# 3V3_EPS.net
KiCad netlist of a schematic drawn in Altium Designer
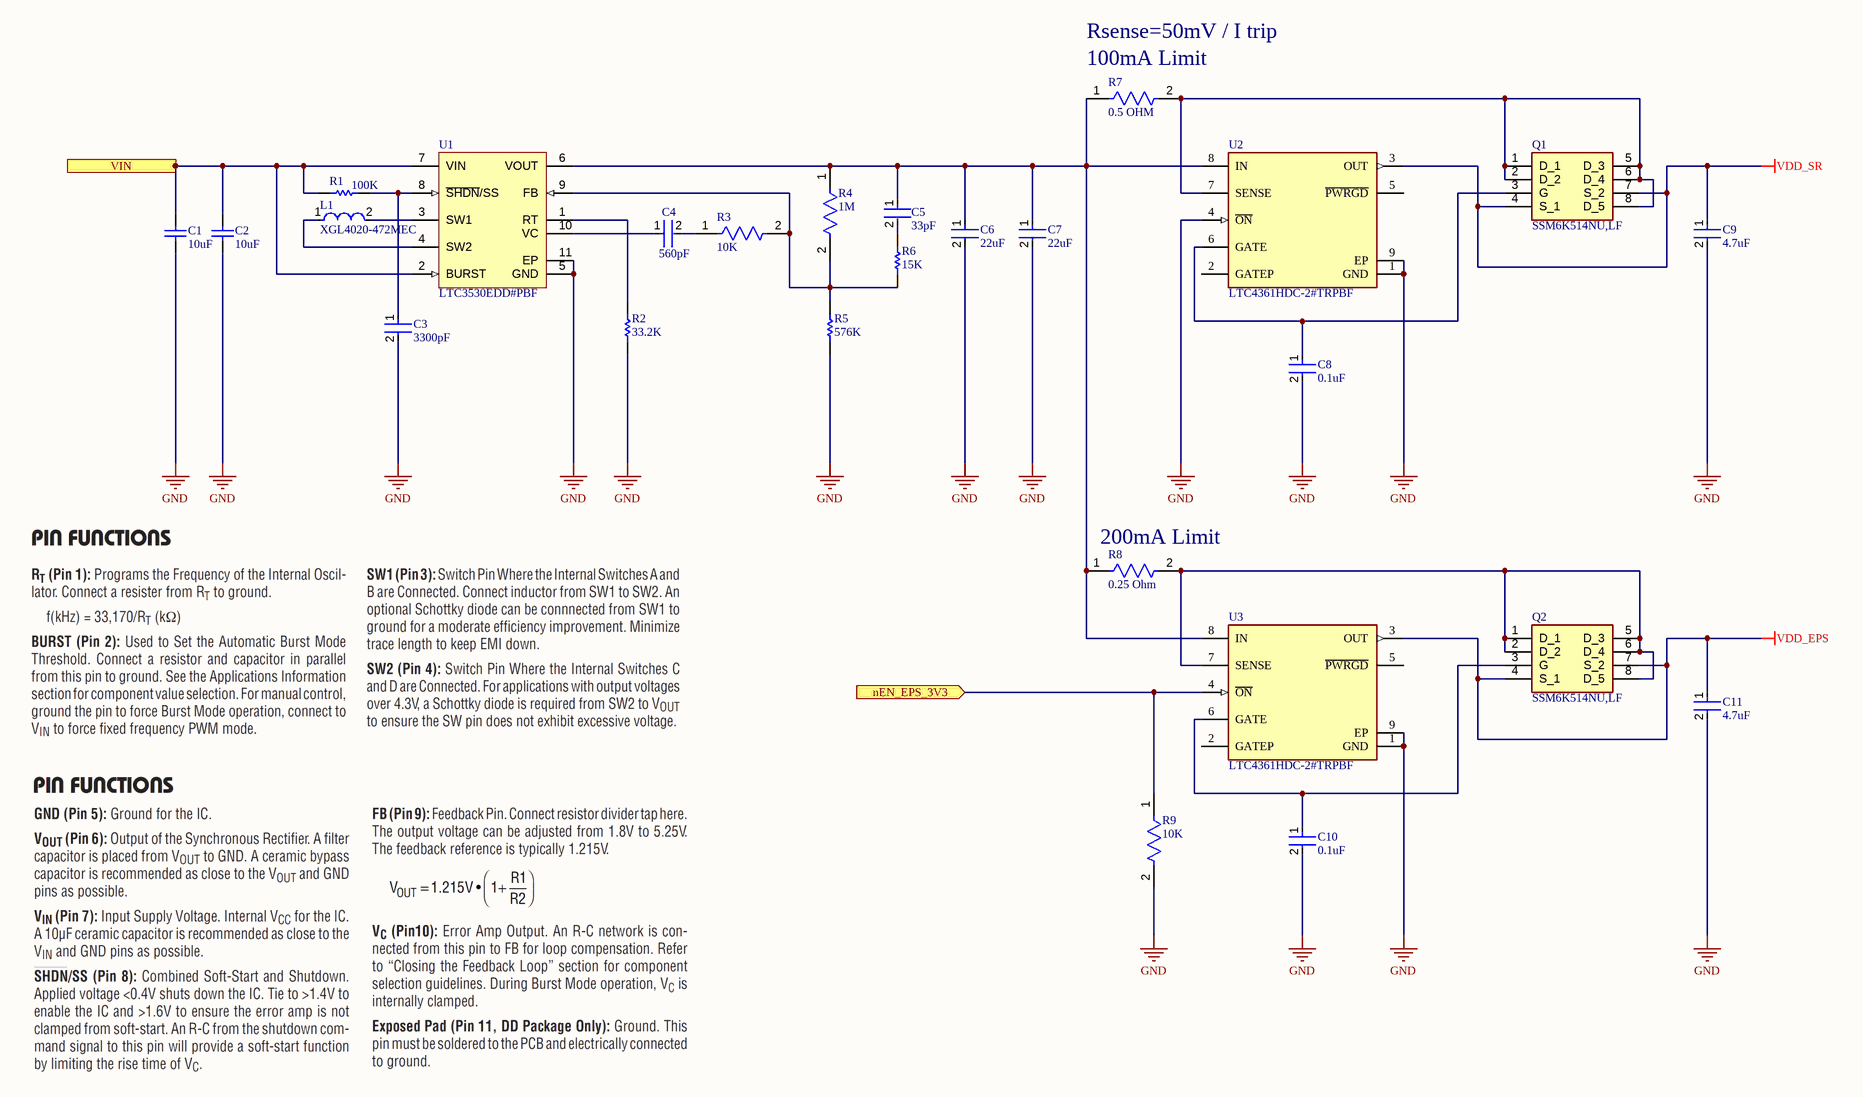
[diagram p0: 3V3_EPS.SchDoc]

(export (version "E")
  (design (tool "Eeschema 10.0.6"))
  (components
    (comp (ref "C1")
      (value "10uF")
      (footprint "CAPC2013X140X45NL15T25")
      (description "10uF 0805")
      (fields (field (name "PART NUMBER") "GRM21BR71A106KE51L") (field (name "MANUFACTURER") "Murata"))
      (libsource (lib "Altium Content Vault") (part "CAP"))
    )
    (comp (ref "C2")
      (value "10uF")
      (footprint "CAPC2013X140X45NL15T25")
      (description "10uF 0805")
      (fields (field (name "PART NUMBER") "GRM21BR71A106KE51L") (field (name "MANUFACTURER") "Murata"))
      (libsource (lib "Altium Content Vault") (part "CAP"))
    )
    (comp (ref "C3")
      (value "3300pF")
      (footprint "FP-C0603C-CF-MFG")
      (description "CAP CER 3300PF 50V 5% X7R 0603")
      (fields
        (field (name "MANUFACTURER PART NUMBER") "C0603C332J5RACTU")
        (field (name "MANUFACTURER") "KEMET")
      )
      (libsource (lib "Altium Content Vault") (part "b4654b650e69147ec39a6b967a45e02"))
    )
    (comp (ref "C4")
      (value "560pF")
      (footprint "FP-C0603C-CF-MFG")
      (description "CAP CER 560PF 50V X7R 0603")
      (fields
        (field (name "TOLERANCE") "0.1")
        (field (name "OCTOPART") "https://octopart.com/c0603c561k5ractu-kemet-138569")
      )
      (libsource (lib "Altium Content Vault") (part "b4654b650e69147ec39a6b967a45e02"))
    )
    (comp (ref "C5")
      (value "33pF")
      (footprint "FP-C0603C-CF-MFG")
      (description "CAP CER 33PF 16V X7R 0603")
      (fields
        (field (name "OCTOPART") "https://octopart.com/c0603c330k4rac7867-kemet-83501964")
        (field (name "MANUFACTURER PART NUMBER") "C0603C330K4RAC7867")
      )
      (libsource (lib "Altium Content Vault") (part "b4654b650e69147ec39a6b967a45e02"))
    )
    (comp (ref "C6")
      (value "22uF")
      (footprint "FP-GRM21B-0_2-e0_2_0_7-IPC_C")
      (description "Chip Multilayer Ceramic Capacitors for General Purpose, 0805, 22uF, X7T, +22%/-33%, 20%, 10V")
      (fields (field (name "VOLTAGE") "10V") (field (name "TOLERANCE") "20%"))
      (libsource (lib "Altium Content Vault") (part "b4654b650e69147ec39a6b967a45e02"))
    )
    (comp (ref "C7")
      (value "22uF")
      (footprint "FP-GRM21B-0_2-e0_2_0_7-IPC_C")
      (description "Chip Multilayer Ceramic Capacitors for General Purpose, 0805, 22uF, X7T, +22%/-33%, 20%, 10V")
      (fields (field (name "VOLTAGE") "10V") (field (name "TOLERANCE") "20%"))
      (libsource (lib "Altium Content Vault") (part "b4654b650e69147ec39a6b967a45e02"))
    )
    (comp (ref "C8")
      (value "0.1uF")
      (footprint "FP-C0603C-CF-MFG")
      (description "CAP CER 0.1UF 16V X7R 0603")
      (fields
        (field (name "OCTOPART") "https://octopart.com/c0603c104j4ractu-kemet-102515")
        (field (name "MANUFACTURER") "KEMET")
      )
      (libsource (lib "Altium Content Vault") (part "b4654b650e69147ec39a6b967a45e02"))
    )
    (comp (ref "C9")
      (value "4.7uF")
      (footprint "FP-GRM188-0_15-IPC_A")
      (description "CAP CER 4.7UF 10V X7S 0603")
      (fields (field (name "TOLERANCE") "10%"))
      (libsource (lib "Altium Content Vault") (part "02cd4be3c70576c341d710602a673aa"))
    )
    (comp (ref "C10")
      (value "0.1uF")
      (footprint "FP-C0603C-CF-MFG")
      (description "CAP CER 0.1UF 16V X7R 0603")
      (fields
        (field (name "OCTOPART") "https://octopart.com/c0603c104j4ractu-kemet-102515")
        (field (name "MANUFACTURER") "KEMET")
      )
      (libsource (lib "Altium Content Vault") (part "b4654b650e69147ec39a6b967a45e02"))
    )
    (comp (ref "C11")
      (value "4.7uF")
      (footprint "FP-GRM188-0_15-IPC_A")
      (description "CAP CER 4.7UF 10V X7S 0603")
      (fields (field (name "TOLERANCE") "10%"))
      (libsource (lib "Altium Content Vault") (part "02cd4be3c70576c341d710602a673aa"))
    )
    (comp (ref "L1")
      (value "XGL4020-472MEC")
      (footprint "FP-XGL4020-MFG")
      (description "Inductor, power, 4.7uH, SMT")
      (fields
        (field (name "MANUFACTURER") "Coilcraft")
        (field (name "OCTOPART") "https://octopart.com/xgl4020-472mec-coilcraft-99681031")
      )
      (libsource (lib "Altium Content Vault") (part "725321dda6339637d4d059423bc1c3c"))
    )
    (comp (ref "Q1")
      (value "SSM6K514NU,LF")
      (footprint "SamacSys:UDFN6B")
      (description "MOSFET (N-Channel)")
      (fields (field (name "MOUSER PART NUMBER") "757-SSM6K514NULF"))
      (libsource (lib "*") (part "SSM6K514NU,LF"))
    )
    (comp (ref "Q2")
      (value "SSM6K514NU,LF")
      (footprint "SamacSys:UDFN6B")
      (description "MOSFET (N-Channel)")
      (fields (field (name "MOUSER PART NUMBER") "757-SSM6K514NULF"))
      (libsource (lib "*") (part "SSM6K514NU,LF"))
    )
    (comp (ref "R1")
      (value "100K")
      (footprint "RESC1608X55X30ML20T10")
      (fields (field (name "PART NUMBER") "RK73B1JTTD104J") (field (name "MANUFACTURER") "KOA Speer"))
      (libsource (lib "Altium Content Vault") (part "RES"))
    )
    (comp (ref "R2")
      (value "33.2K")
      (footprint "RESC1608X55X30NL15T15")
      (fields (field (name "PART NUMBER") "ERJ-3EKF3322V") (field (name "MANUFACTURER") "Panasonic"))
      (libsource (lib "Altium Content Vault") (part "RES"))
    )
    (comp (ref "R3")
      (value "10K")
      (footprint "FP-RK73B1J-MFG")
      (description "RES 10K OHM 5% 1/10W 0603")
      (fields (field (name "TOLERANCE") "5%"))
      (libsource (lib "Altium Content Vault") (part "1029c3af85768c4190bb7ad29bc67b5"))
    )
    (comp (ref "R4")
      (value "1M")
      (footprint "FP-ERJ3EK-IPC_C")
      (description "RES SMD 1M OHM 1% 1/10W 0603")
      (fields (field (name "TOLERANCE") "1%"))
      (libsource (lib "Altium Content Vault") (part "1029c3af85768c4190bb7ad29bc67b5"))
    )
    (comp (ref "R5")
      (value "576K")
      (footprint "RESC1608X55X30LL15T15")
      (description "576K Ohm 0603")
      (fields (field (name "PART NUMBER") "ERJ-3EKF5763V") (field (name "MANUFACTURER") "Panasonic"))
      (libsource (lib "Altium Content Vault") (part "RES"))
    )
    (comp (ref "R6")
      (value "15K")
      (footprint "RESC1608X55X30NL20T10")
      (description "15K Ohm 0603")
      (fields (field (name "PART NUMBER") "RK73B1JTTD153J") (field (name "MANUFACTURER") "KOA Speer"))
      (libsource (lib "Altium Content Vault") (part "RES"))
    )
    (comp (ref "R7")
      (value "0.5 OHM")
      (footprint "FP-CSR0603-IPC_A")
      (description "General Purpose Thick Film Chip Resistor, 0603, 0.5Ω, 1%, 300ppm/°C, 0.125W")
      (fields (field (name "TOLERANCE") "1%"))
      (libsource (lib "Altium Content Vault") (part "1029c3af85768c4190bb7ad29bc67b5"))
    )
    (comp (ref "R8")
      (value "0.25 Ohm")
      (footprint "FP-CSR0603-IPC_A")
      (description "General Purpose Thick Film Chip Resistor, 0603, 0.25Ω, 1%, 300ppm/°C, 0.125W")
      (fields (field (name "TOLERANCE") "1%"))
      (libsource (lib "Altium Content Vault") (part "1029c3af85768c4190bb7ad29bc67b5"))
    )
    (comp (ref "R9")
      (value "10K")
      (footprint "FP-RK73B1J-MFG")
      (description "RES 10K OHM 5% 1/10W 0603")
      (fields (field (name "TOLERANCE") "5%"))
      (libsource (lib "Altium Content Vault") (part "1029c3af85768c4190bb7ad29bc67b5"))
    )
    (comp (ref "U1")
      (value "LTC3530EDD#PBF")
      (footprint "LT-DD-10_V")
      (fields (field (name "MANUFACTURER") "Linear Technology"))
      (libsource (lib "Altium Content Vault") (part "LT-LTC3530-DD-10"))
    )
    (comp (ref "U2")
      (value "LTC4361HDC-2#TRPBF")
      (footprint "FP-DC8-8-05-08-1719-IPC_C")
      (description "IC OVP/OCP PROTECTION CTLR 8DFN")
      (libsource (lib "Altium Content Vault") (part "fbb45dfe5e09bf71f23ab0fd2a2f1dd"))
    )
    (comp (ref "U3")
      (value "LTC4361HDC-2#TRPBF")
      (footprint "FP-DC8-8-05-08-1719-IPC_C")
      (description "IC OVP/OCP PROTECTION CTLR 8DFN")
      (libsource (lib "Altium Content Vault") (part "fbb45dfe5e09bf71f23ab0fd2a2f1dd"))
    )
  )
  (nets
    (net (code "1") (name "/VIN") (class "Default")
      (node (ref "C1") (pin "2") (pinfunction "2_2") (pintype "passive"))
      (node (ref "C2") (pin "2") (pinfunction "2_2") (pintype "passive"))
      (node (ref "R1") (pin "2") (pinfunction "2_2") (pintype "passive"))
      (node (ref "U1") (pin "2") (pinfunction "BURST_2") (pintype "input"))
      (node (ref "U1") (pin "7") (pinfunction "VIN_7") (pintype "power_in"))
    )
    (net (code "2") (name "/nEN_EPS_3V3") (class "Default")
      (node (ref "R9") (pin "1") (pinfunction "1_1") (pintype "passive"))
      (node (ref "U3") (pin "4") (pinfunction "~{ON}_4") (pintype "input"))
    )
    (net (code "3") (name "GND") (class "Default")
      (node (ref "C1") (pin "1") (pinfunction "1_1") (pintype "passive"))
      (node (ref "C10") (pin "2") (pinfunction "2_2") (pintype "passive"))
      (node (ref "C11") (pin "2") (pinfunction "2_2") (pintype "passive"))
      (node (ref "C2") (pin "1") (pinfunction "1_1") (pintype "passive"))
      (node (ref "C3") (pin "2") (pinfunction "2_2") (pintype "passive"))
      (node (ref "C6") (pin "2") (pinfunction "2_2") (pintype "passive"))
      (node (ref "C7") (pin "2") (pinfunction "2_2") (pintype "passive"))
      (node (ref "C8") (pin "2") (pinfunction "2_2") (pintype "passive"))
      (node (ref "C9") (pin "2") (pinfunction "2_2") (pintype "passive"))
      (node (ref "R2") (pin "1") (pinfunction "1_1") (pintype "passive"))
      (node (ref "R5") (pin "1") (pinfunction "1_1") (pintype "passive"))
      (node (ref "R9") (pin "2") (pinfunction "2_2") (pintype "passive"))
      (node (ref "U1") (pin "11") (pinfunction "EP_11") (pintype "power_in"))
      (node (ref "U1") (pin "5") (pinfunction "GND_5") (pintype "power_in"))
      (node (ref "U2") (pin "1") (pinfunction "GND_1") (pintype "power_in"))
      (node (ref "U2") (pin "4") (pinfunction "~{ON}_4") (pintype "input"))
      (node (ref "U2") (pin "9") (pinfunction "EP_9") (pintype "power_in"))
      (node (ref "U3") (pin "1") (pinfunction "GND_1") (pintype "power_in"))
      (node (ref "U3") (pin "9") (pinfunction "EP_9") (pintype "power_in"))
    )
    (net (code "4") (name "Net-(C4-Pad2)") (class "Default")
      (node (ref "C4") (pin "2") (pinfunction "2_2") (pintype "passive"))
      (node (ref "R3") (pin "1") (pinfunction "1_1") (pintype "passive"))
    )
    (net (code "5") (name "Net-(C5-Pad2)") (class "Default")
      (node (ref "C5") (pin "2") (pinfunction "2_2") (pintype "passive"))
      (node (ref "R6") (pin "2") (pinfunction "2_2") (pintype "passive"))
    )
    (net (code "6") (name "Net-(Q1-D_1)") (class "Default")
      (node (ref "Q1") (pin "1") (pinfunction "D_1_1") (pintype "passive"))
      (node (ref "Q1") (pin "2") (pinfunction "D_2_2") (pintype "passive"))
      (node (ref "Q1") (pin "5") (pinfunction "D_3_5") (pintype "passive"))
      (node (ref "Q1") (pin "6") (pinfunction "D_4_6") (pintype "passive"))
      (node (ref "Q1") (pin "8") (pinfunction "D_5_8") (pintype "passive"))
      (node (ref "R7") (pin "2") (pinfunction "2_2") (pintype "passive"))
      (node (ref "U2") (pin "7") (pinfunction "SENSE_7") (pintype "passive"))
    )
    (net (code "7") (name "Net-(Q1-G)") (class "Default")
      (node (ref "C8") (pin "1") (pinfunction "1_1") (pintype "passive"))
      (node (ref "Q1") (pin "3") (pinfunction "G_3") (pintype "passive"))
      (node (ref "U2") (pin "6") (pinfunction "GATE_6") (pintype "passive"))
    )
    (net (code "8") (name "Net-(Q2-D_1)") (class "Default")
      (node (ref "Q2") (pin "1") (pinfunction "D_1_1") (pintype "passive"))
      (node (ref "Q2") (pin "2") (pinfunction "D_2_2") (pintype "passive"))
      (node (ref "Q2") (pin "5") (pinfunction "D_3_5") (pintype "passive"))
      (node (ref "Q2") (pin "6") (pinfunction "D_4_6") (pintype "passive"))
      (node (ref "Q2") (pin "8") (pinfunction "D_5_8") (pintype "passive"))
      (node (ref "R8") (pin "2") (pinfunction "2_2") (pintype "passive"))
      (node (ref "U3") (pin "7") (pinfunction "SENSE_7") (pintype "passive"))
    )
    (net (code "9") (name "Net-(Q2-G)") (class "Default")
      (node (ref "C10") (pin "1") (pinfunction "1_1") (pintype "passive"))
      (node (ref "Q2") (pin "3") (pinfunction "G_3") (pintype "passive"))
      (node (ref "U3") (pin "6") (pinfunction "GATE_6") (pintype "passive"))
    )
    (net (code "10") (name "Net-(U1-FB)") (class "Default")
      (node (ref "R3") (pin "2") (pinfunction "2_2") (pintype "passive"))
      (node (ref "R4") (pin "2") (pinfunction "2_2") (pintype "passive"))
      (node (ref "R5") (pin "2") (pinfunction "2_2") (pintype "passive"))
      (node (ref "R6") (pin "1") (pinfunction "1_1") (pintype "passive"))
      (node (ref "U1") (pin "9") (pinfunction "FB_9") (pintype "input"))
    )
    (net (code "11") (name "Net-(U1-RT)") (class "Default")
      (node (ref "R2") (pin "2") (pinfunction "2_2") (pintype "passive"))
      (node (ref "U1") (pin "1") (pinfunction "RT_1") (pintype "passive"))
    )
    (net (code "12") (name "Net-(U1-SW1)") (class "Default")
      (node (ref "L1") (pin "2") (pinfunction "2_2") (pintype "passive"))
      (node (ref "U1") (pin "3") (pinfunction "SW1_3") (pintype "passive"))
    )
    (net (code "13") (name "Net-(U1-SW2)") (class "Default")
      (node (ref "L1") (pin "1") (pinfunction "1_1") (pintype "passive"))
      (node (ref "U1") (pin "4") (pinfunction "SW2_4") (pintype "passive"))
    )
    (net (code "14") (name "Net-(U1-VC)") (class "Default")
      (node (ref "C4") (pin "1") (pinfunction "1_1") (pintype "passive"))
      (node (ref "U1") (pin "10") (pinfunction "VC_10") (pintype "passive"))
    )
    (net (code "15") (name "Net-(U1-VOUT)") (class "Default")
      (node (ref "C5") (pin "1") (pinfunction "1_1") (pintype "passive"))
      (node (ref "C6") (pin "1") (pinfunction "1_1") (pintype "passive"))
      (node (ref "C7") (pin "1") (pinfunction "1_1") (pintype "passive"))
      (node (ref "R4") (pin "1") (pinfunction "1_1") (pintype "passive"))
      (node (ref "R7") (pin "1") (pinfunction "1_1") (pintype "passive"))
      (node (ref "R8") (pin "1") (pinfunction "1_1") (pintype "passive"))
      (node (ref "U1") (pin "6") (pinfunction "VOUT_6") (pintype "power_in"))
      (node (ref "U2") (pin "8") (pinfunction "IN_8") (pintype "power_in"))
      (node (ref "U3") (pin "8") (pinfunction "IN_8") (pintype "power_in"))
    )
    (net (code "16") (name "Net-(U1-~{SHDN}{slash}SS)") (class "Default")
      (node (ref "C3") (pin "1") (pinfunction "1_1") (pintype "passive"))
      (node (ref "R1") (pin "1") (pinfunction "1_1") (pintype "passive"))
      (node (ref "U1") (pin "8") (pinfunction "~{SHDN}/SS_8") (pintype "input"))
    )
    (net (code "17") (name "VDD_EPS") (class "Default")
      (node (ref "C11") (pin "1") (pinfunction "1_1") (pintype "passive"))
      (node (ref "Q2") (pin "4") (pinfunction "S_1_4") (pintype "passive"))
      (node (ref "Q2") (pin "7") (pinfunction "S_2_7") (pintype "passive"))
      (node (ref "U3") (pin "3") (pinfunction "OUT_3") (pintype "output"))
    )
    (net (code "18") (name "VDD_SR") (class "Default")
      (node (ref "C9") (pin "1") (pinfunction "1_1") (pintype "passive"))
      (node (ref "Q1") (pin "4") (pinfunction "S_1_4") (pintype "passive"))
      (node (ref "Q1") (pin "7") (pinfunction "S_2_7") (pintype "passive"))
      (node (ref "U2") (pin "3") (pinfunction "OUT_3") (pintype "output"))
    )
    (net (code "19") (name "unconnected-(U2-GATEP-Pad2)") (class "Default")
      (node (ref "U2") (pin "2") (pinfunction "GATEP_2") (pintype "passive"))
    )
    (net (code "20") (name "unconnected-(U2-~{PWRGD}-Pad5)") (class "Default")
      (node (ref "U2") (pin "5") (pinfunction "~{PWRGD}_5") (pintype "open_collector"))
    )
    (net (code "21") (name "unconnected-(U3-GATEP-Pad2)") (class "Default")
      (node (ref "U3") (pin "2") (pinfunction "GATEP_2") (pintype "passive"))
    )
    (net (code "22") (name "unconnected-(U3-~{PWRGD}-Pad5)") (class "Default")
      (node (ref "U3") (pin "5") (pinfunction "~{PWRGD}_5") (pintype "open_collector"))
    )
  )
)
